# satshakit_power_board.net
KiCad netlist of a schematic drawn in EAGLE
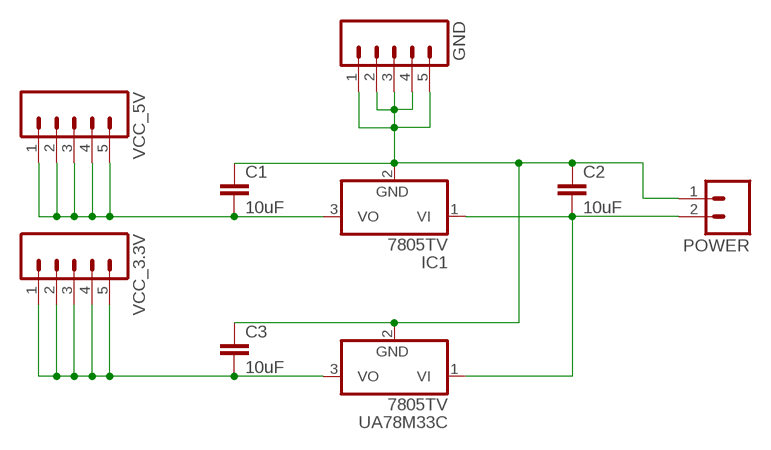
[diagram p0: schematic, sheet 1]

(export (version "E")
  (design (tool "Eeschema 10.0.6"))
  (components
    (comp (ref "C1")
      (value "10uF")
      (footprint "eagle-import:1206")
      (libsource (lib "eagle-import") (part "CAP1206"))
    )
    (comp (ref "C2")
      (value "10uF")
      (footprint "eagle-import:1206")
      (libsource (lib "eagle-import") (part "CAP1206"))
    )
    (comp (ref "C3")
      (value "10uF")
      (footprint "eagle-import:1206")
      (libsource (lib "eagle-import") (part "CAP1206"))
    )
    (comp (ref "GND")
      (value "M05PTH_LONGPADS")
      (footprint "eagle-import:1X05_LONGPADS")
      (libsource (lib "eagle-import") (part "M05PTH_LONGPADS"))
    )
    (comp (ref "IC1")
      (value "7805TV")
      (footprint "eagle-import:TO220V")
      (libsource (lib "eagle-import") (part "78TV05"))
    )
    (comp (ref "POWER")
      (value "M02")
      (footprint "eagle-import:1X02_LONGPADS")
      (libsource (lib "eagle-import") (part "M02"))
    )
    (comp (ref "UA78M33C")
      (value "7805TV")
      (footprint "eagle-import:TO220V")
      (libsource (lib "eagle-import") (part "78TV05"))
    )
    (comp (ref "VCC_3.3V")
      (value "M05PTH_LONGPADS")
      (footprint "eagle-import:1X05_LONGPADS")
      (libsource (lib "eagle-import") (part "M05PTH_LONGPADS"))
    )
    (comp (ref "VCC_5V")
      (value "M05PTH_LONGPADS")
      (footprint "eagle-import:1X05_LONGPADS")
      (libsource (lib "eagle-import") (part "M05PTH_LONGPADS"))
    )
  )
  (nets
    (net (code "1") (name "Net-(IC1-GND)") (class "Default")
      (node (ref "C1") (pin "1") (pinfunction "1_1") (pintype "passive"))
      (node (ref "C2") (pin "1") (pinfunction "1_1") (pintype "passive"))
      (node (ref "C3") (pin "1") (pinfunction "1_1") (pintype "passive"))
      (node (ref "GND") (pin "1") (pinfunction "1_1") (pintype "passive"))
      (node (ref "GND") (pin "2") (pinfunction "2_2") (pintype "passive"))
      (node (ref "GND") (pin "3") (pinfunction "3_3") (pintype "passive"))
      (node (ref "GND") (pin "4") (pinfunction "4_4") (pintype "passive"))
      (node (ref "GND") (pin "5") (pinfunction "5_5") (pintype "passive"))
      (node (ref "IC1") (pin "2") (pinfunction "GND_2") (pintype "passive"))
      (node (ref "POWER") (pin "1") (pinfunction "1_1") (pintype "passive"))
      (node (ref "UA78M33C") (pin "2") (pinfunction "GND_2") (pintype "passive"))
    )
    (net (code "2") (name "Net-(IC1-VI)") (class "Default")
      (node (ref "C2") (pin "2") (pinfunction "2_2") (pintype "passive"))
      (node (ref "IC1") (pin "1") (pinfunction "VI_1") (pintype "input"))
      (node (ref "POWER") (pin "2") (pinfunction "2_2") (pintype "passive"))
      (node (ref "UA78M33C") (pin "1") (pinfunction "VI_1") (pintype "input"))
    )
    (net (code "3") (name "Net-(IC1-VO)") (class "Default")
      (node (ref "C1") (pin "2") (pinfunction "2_2") (pintype "passive"))
      (node (ref "IC1") (pin "3") (pinfunction "VO_3") (pintype "passive"))
      (node (ref "VCC_5V") (pin "1") (pinfunction "1_1") (pintype "passive"))
      (node (ref "VCC_5V") (pin "2") (pinfunction "2_2") (pintype "passive"))
      (node (ref "VCC_5V") (pin "3") (pinfunction "3_3") (pintype "passive"))
      (node (ref "VCC_5V") (pin "4") (pinfunction "4_4") (pintype "passive"))
      (node (ref "VCC_5V") (pin "5") (pinfunction "5_5") (pintype "passive"))
    )
    (net (code "4") (name "Net-(UA78M33C-VO)") (class "Default")
      (node (ref "C3") (pin "2") (pinfunction "2_2") (pintype "passive"))
      (node (ref "UA78M33C") (pin "3") (pinfunction "VO_3") (pintype "passive"))
      (node (ref "VCC_3.3V") (pin "1") (pinfunction "1_1") (pintype "passive"))
      (node (ref "VCC_3.3V") (pin "2") (pinfunction "2_2") (pintype "passive"))
      (node (ref "VCC_3.3V") (pin "3") (pinfunction "3_3") (pintype "passive"))
      (node (ref "VCC_3.3V") (pin "4") (pinfunction "4_4") (pintype "passive"))
      (node (ref "VCC_3.3V") (pin "5") (pinfunction "5_5") (pintype "passive"))
    )
  )
)
